# LT3060XDC_45V_to_1V8.net
KiCad netlist of a schematic drawn in EAGLE
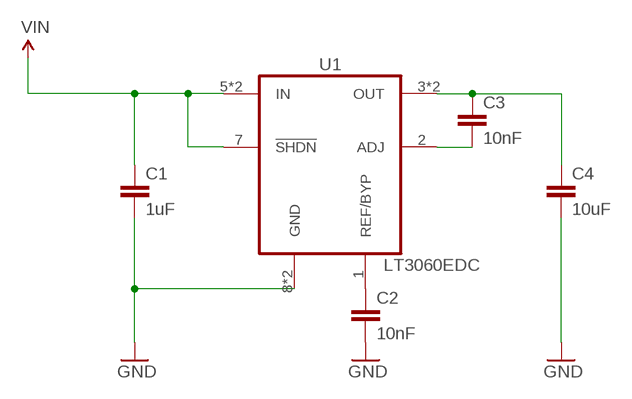
[diagram p0: schematic, sheet 1]

(export (version "E")
  (design (tool "Eeschema 10.0.6"))
  (components
    (comp (ref "C1")
      (value "1uF")
      (footprint "eagle-import:C0402")
      (libsource (lib "eagle-import") (part "C-EUC0402"))
    )
    (comp (ref "C2")
      (value "10nF")
      (footprint "eagle-import:C0402")
      (libsource (lib "eagle-import") (part "C-EUC0402"))
    )
    (comp (ref "C3")
      (value "10nF")
      (footprint "eagle-import:C0402")
      (libsource (lib "eagle-import") (part "C-EUC0402"))
    )
    (comp (ref "C4")
      (value "10uF")
      (footprint "eagle-import:C0402")
      (libsource (lib "eagle-import") (part "C-EUC0402"))
    )
    (comp (ref "U1")
      (value "LT3060EDC")
      (footprint "eagle-import:LINEAR_DC8")
      (libsource (lib "eagle-import") (part "LT3060DCE"))
    )
  )
  (nets
    (net (code "1") (name "GND") (class "Default")
      (node (ref "C1") (pin "2") (pinfunction "2_2") (pintype "passive"))
      (node (ref "C2") (pin "2") (pinfunction "2_2") (pintype "passive"))
      (node (ref "C4") (pin "2") (pinfunction "2_2") (pintype "passive"))
      (node (ref "U1") (pin "8") (pinfunction "GND_8") (pintype "passive"))
      (node (ref "U1") (pin "9") (pinfunction "GND_9") (pintype "passive"))
    )
    (net (code "2") (name "Net-(C3-Pad1)") (class "Default")
      (node (ref "C3") (pin "1") (pinfunction "1_1") (pintype "passive"))
      (node (ref "C4") (pin "1") (pinfunction "1_1") (pintype "passive"))
      (node (ref "U1") (pin "3") (pinfunction "OUT_3") (pintype "power_in"))
      (node (ref "U1") (pin "4") (pinfunction "OUT_4") (pintype "power_in"))
    )
    (net (code "3") (name "Net-(U1-ADJ)") (class "Default")
      (node (ref "C3") (pin "2") (pinfunction "2_2") (pintype "passive"))
      (node (ref "U1") (pin "2") (pinfunction "ADJ_2") (pintype "input"))
    )
    (net (code "4") (name "Net-(U1-REF{slash}BYP)") (class "Default")
      (node (ref "C2") (pin "1") (pinfunction "1_1") (pintype "passive"))
      (node (ref "U1") (pin "1") (pinfunction "REF/BYP_1") (pintype "input"))
    )
    (net (code "5") (name "VIN") (class "Default")
      (node (ref "C1") (pin "1") (pinfunction "1_1") (pintype "passive"))
      (node (ref "U1") (pin "5") (pinfunction "IN_5") (pintype "power_in"))
      (node (ref "U1") (pin "6") (pinfunction "IN_6") (pintype "power_in"))
      (node (ref "U1") (pin "7") (pinfunction "~{SHDN}_7") (pintype "input"))
    )
  )
)
